# schema_puissance.net
KiCad netlist of a schematic drawn in EAGLE
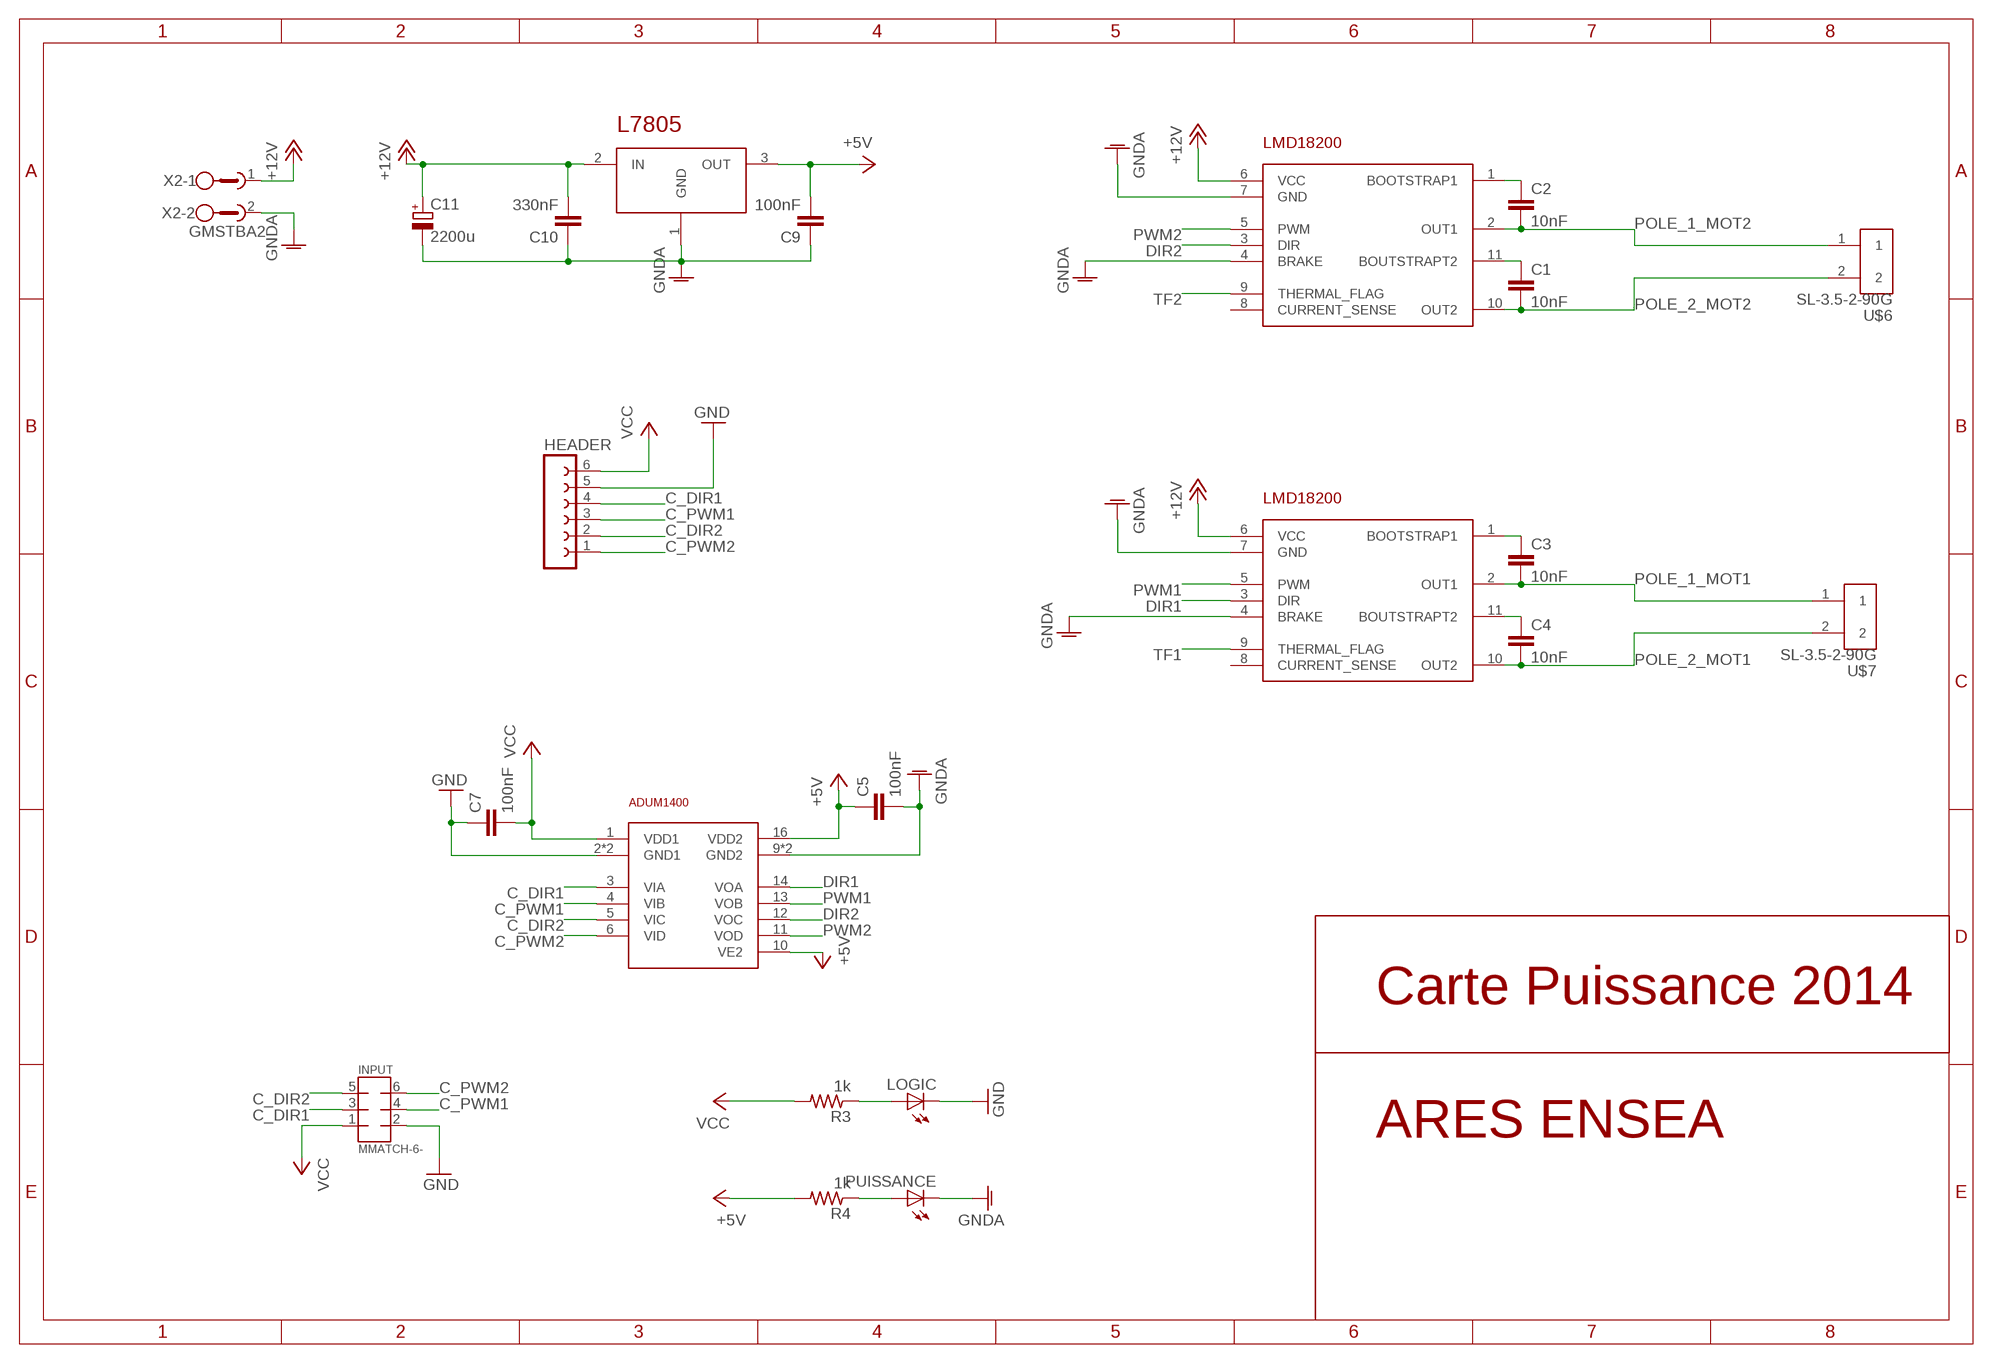
[diagram p0: schematic, sheet 1]

(export (version "E")
  (design (tool "Eeschema 10.0.6"))
  (components
    (comp (ref "C1")
      (value "10nF")
      (footprint "eagle-import:C0805")
      (libsource (lib "eagle-import") (part "C-EUC0805"))
    )
    (comp (ref "C2")
      (value "10nF")
      (footprint "eagle-import:C0805")
      (libsource (lib "eagle-import") (part "C-EUC0805"))
    )
    (comp (ref "C3")
      (value "10nF")
      (footprint "eagle-import:C0805")
      (libsource (lib "eagle-import") (part "C-EUC0805"))
    )
    (comp (ref "C4")
      (value "10nF")
      (footprint "eagle-import:C0805")
      (libsource (lib "eagle-import") (part "C-EUC0805"))
    )
    (comp (ref "C5")
      (value "100nF")
      (footprint "eagle-import:C0805")
      (libsource (lib "eagle-import") (part "C-EUC0805"))
    )
    (comp (ref "C7")
      (value "100nF")
      (footprint "eagle-import:C0805")
      (libsource (lib "eagle-import") (part "C-EUC0805"))
    )
    (comp (ref "C9")
      (value "100nF")
      (footprint "eagle-import:C0805")
      (libsource (lib "eagle-import") (part "C-EUC0805"))
    )
    (comp (ref "C10")
      (value "330nF")
      (footprint "eagle-import:C0805")
      (libsource (lib "eagle-import") (part "C-EUC0805"))
    )
    (comp (ref "C11")
      (value "2200u")
      (footprint "eagle-import:TT5D11")
      (libsource (lib "eagle-import") (part "CPOL-EUTT5D11"))
    )
    (comp (ref "HEADER")
      (value "FE06-1")
      (footprint "eagle-import:FE06")
      (libsource (lib "eagle-import") (part "FE06-1"))
    )
    (comp (ref "INPUT")
      (value "MMATCH-6-")
      (footprint "eagle-import:AMP-215079-6")
      (libsource (lib "eagle-import") (part "MMATCH-6-"))
    )
    (comp (ref "LOGIC")
      (value "LEDSML0805")
      (footprint "eagle-import:SML0805")
      (libsource (lib "eagle-import") (part "LEDSML0805"))
    )
    (comp (ref "PUISSANCE")
      (value "LEDSML0805")
      (footprint "eagle-import:SML0805")
      (libsource (lib "eagle-import") (part "LEDSML0805"))
    )
    (comp (ref "R3")
      (value "1k")
      (footprint "eagle-import:M0805")
      (libsource (lib "eagle-import") (part "R-US_M0805"))
    )
    (comp (ref "R4")
      (value "1k")
      (footprint "eagle-import:M0805")
      (libsource (lib "eagle-import") (part "R-US_M0805"))
    )
    (comp (ref "U$1")
      (value "LMD18200")
      (footprint "eagle-import:LMD18200")
      (libsource (lib "eagle-import") (part "LMD18200"))
    )
    (comp (ref "U$2")
      (value "LMD18200")
      (footprint "eagle-import:LMD18200")
      (libsource (lib "eagle-import") (part "LMD18200"))
    )
    (comp (ref "U$3")
      (value "ADUM1400S")
      (footprint "eagle-import:SO-16W")
      (libsource (lib "eagle-import") (part "ADUM1400S"))
    )
    (comp (ref "U$5")
      (value "L7805TO263")
      (footprint "eagle-import:DPAK")
      (libsource (lib "eagle-import") (part "L7805TO263"))
    )
    (comp (ref "U$6")
      (value "SL-3.5-2-90G")
      (footprint "eagle-import:SL-3.5-2-90G")
      (libsource (lib "eagle-import") (part "SL-3.5-2-90G"))
    )
    (comp (ref "U$7")
      (value "SL-3.5-2-90G")
      (footprint "eagle-import:SL-3.5-2-90G")
      (libsource (lib "eagle-import") (part "SL-3.5-2-90G"))
    )
    (comp (ref "X2")
      (value "GMSTBA2")
      (footprint "eagle-import:GMSTBA2")
      (fields (field (name "MF") "FARNELL") (field (name "MPN") "1757242"))
      (libsource (lib "eagle-import") (part "GMSTBA2"))
    )
  )
  (nets
    (net (code "1") (name "+5V") (class "Default")
      (node (ref "C5") (pin "1") (pinfunction "1_1") (pintype "passive"))
      (node (ref "C9") (pin "2") (pinfunction "2_2") (pintype "passive"))
      (node (ref "R4") (pin "2") (pinfunction "2_2") (pintype "passive"))
      (node (ref "U$3") (pin "10") (pinfunction "VE2_10") (pintype "bidirectional"))
      (node (ref "U$3") (pin "16") (pinfunction "VDD2_16") (pintype "bidirectional"))
      (node (ref "U$5") (pin "3") (pinfunction "OUT_3") (pintype "bidirectional"))
    )
    (net (code "2") (name "+12V") (class "Default")
      (node (ref "C10") (pin "2") (pinfunction "2_2") (pintype "passive"))
      (node (ref "C11") (pin "+") (pinfunction "+_+") (pintype "passive"))
      (node (ref "U$1") (pin "6") (pinfunction "VCC_6") (pintype "bidirectional"))
      (node (ref "U$2") (pin "6") (pinfunction "VCC_6") (pintype "bidirectional"))
      (node (ref "U$5") (pin "2") (pinfunction "IN_2") (pintype "bidirectional"))
      (node (ref "X2") (pin "1") (pinfunction "1_1") (pintype "passive"))
    )
    (net (code "3") (name "/C_DIR1") (class "Default")
      (node (ref "HEADER") (pin "4") (pinfunction "4_4") (pintype "passive"))
      (node (ref "INPUT") (pin "3") (pinfunction "5_3") (pintype "bidirectional"))
      (node (ref "U$3") (pin "3") (pinfunction "VIA_3") (pintype "bidirectional"))
    )
    (net (code "4") (name "/C_DIR2") (class "Default")
      (node (ref "HEADER") (pin "2") (pinfunction "2_2") (pintype "passive"))
      (node (ref "INPUT") (pin "5") (pinfunction "7_5") (pintype "bidirectional"))
      (node (ref "U$3") (pin "5") (pinfunction "VIC_5") (pintype "bidirectional"))
    )
    (net (code "5") (name "/C_PWM1") (class "Default")
      (node (ref "HEADER") (pin "3") (pinfunction "3_3") (pintype "passive"))
      (node (ref "INPUT") (pin "4") (pinfunction "6_4") (pintype "bidirectional"))
      (node (ref "U$3") (pin "4") (pinfunction "VIB_4") (pintype "bidirectional"))
    )
    (net (code "6") (name "/C_PWM2") (class "Default")
      (node (ref "HEADER") (pin "1") (pinfunction "1_1") (pintype "passive"))
      (node (ref "INPUT") (pin "6") (pinfunction "8_6") (pintype "bidirectional"))
      (node (ref "U$3") (pin "6") (pinfunction "VID_6") (pintype "bidirectional"))
    )
    (net (code "7") (name "/DIR1") (class "Default")
      (node (ref "U$1") (pin "3") (pinfunction "DIR_3") (pintype "bidirectional"))
      (node (ref "U$3") (pin "14") (pinfunction "VOA_14") (pintype "bidirectional"))
    )
    (net (code "8") (name "/DIR2") (class "Default")
      (node (ref "U$2") (pin "3") (pinfunction "DIR_3") (pintype "bidirectional"))
      (node (ref "U$3") (pin "12") (pinfunction "VOC_12") (pintype "bidirectional"))
    )
    (net (code "9") (name "/POLE_1_MOT1") (class "Default")
      (node (ref "C3") (pin "2") (pinfunction "2_2") (pintype "passive"))
      (node (ref "U$1") (pin "2") (pinfunction "OUT1_2") (pintype "bidirectional"))
      (node (ref "U$7") (pin "1") (pinfunction "1_1") (pintype "bidirectional"))
    )
    (net (code "10") (name "/POLE_1_MOT2") (class "Default")
      (node (ref "C2") (pin "2") (pinfunction "2_2") (pintype "passive"))
      (node (ref "U$2") (pin "2") (pinfunction "OUT1_2") (pintype "bidirectional"))
      (node (ref "U$6") (pin "1") (pinfunction "1_1") (pintype "bidirectional"))
    )
    (net (code "11") (name "/POLE_2_MOT1") (class "Default")
      (node (ref "C4") (pin "2") (pinfunction "2_2") (pintype "passive"))
      (node (ref "U$1") (pin "10") (pinfunction "OUT2_10") (pintype "bidirectional"))
      (node (ref "U$7") (pin "2") (pinfunction "2_2") (pintype "bidirectional"))
    )
    (net (code "12") (name "/POLE_2_MOT2") (class "Default")
      (node (ref "C1") (pin "2") (pinfunction "2_2") (pintype "passive"))
      (node (ref "U$2") (pin "10") (pinfunction "OUT2_10") (pintype "bidirectional"))
      (node (ref "U$6") (pin "2") (pinfunction "2_2") (pintype "bidirectional"))
    )
    (net (code "13") (name "/PWM1") (class "Default")
      (node (ref "U$1") (pin "5") (pinfunction "PWM_5") (pintype "bidirectional"))
      (node (ref "U$3") (pin "13") (pinfunction "VOB_13") (pintype "bidirectional"))
    )
    (net (code "14") (name "/PWM2") (class "Default")
      (node (ref "U$2") (pin "5") (pinfunction "PWM_5") (pintype "bidirectional"))
      (node (ref "U$3") (pin "11") (pinfunction "VOD_11") (pintype "bidirectional"))
    )
    (net (code "15") (name "/TF1") (class "Default")
      (node (ref "U$1") (pin "9") (pinfunction "THERMAL_FLAG_9") (pintype "bidirectional"))
    )
    (net (code "16") (name "/TF2") (class "Default")
      (node (ref "U$2") (pin "9") (pinfunction "THERMAL_FLAG_9") (pintype "bidirectional"))
    )
    (net (code "17") (name "GND") (class "Default")
      (node (ref "C7") (pin "1") (pinfunction "1_1") (pintype "passive"))
      (node (ref "HEADER") (pin "5") (pinfunction "5_5") (pintype "passive"))
      (node (ref "INPUT") (pin "2") (pinfunction "4_2") (pintype "bidirectional"))
      (node (ref "LOGIC") (pin "C") (pinfunction "C_C") (pintype "passive"))
      (node (ref "U$3") (pin "2") (pinfunction "GND1_2") (pintype "bidirectional"))
      (node (ref "U$3") (pin "8") (pinfunction "GND1_8") (pintype "bidirectional"))
    )
    (net (code "18") (name "GNDA") (class "Default")
      (node (ref "C10") (pin "1") (pinfunction "1_1") (pintype "passive"))
      (node (ref "C11") (pin "-") (pinfunction "-_-") (pintype "passive"))
      (node (ref "C5") (pin "2") (pinfunction "2_2") (pintype "passive"))
      (node (ref "C9") (pin "1") (pinfunction "1_1") (pintype "passive"))
      (node (ref "PUISSANCE") (pin "C") (pinfunction "C_C") (pintype "passive"))
      (node (ref "U$1") (pin "4") (pinfunction "BRAKE_4") (pintype "bidirectional"))
      (node (ref "U$1") (pin "7") (pinfunction "GND_7") (pintype "bidirectional"))
      (node (ref "U$2") (pin "4") (pinfunction "BRAKE_4") (pintype "bidirectional"))
      (node (ref "U$2") (pin "7") (pinfunction "GND_7") (pintype "bidirectional"))
      (node (ref "U$3") (pin "15") (pinfunction "GND2_15") (pintype "bidirectional"))
      (node (ref "U$3") (pin "9") (pinfunction "GND2_9") (pintype "bidirectional"))
      (node (ref "U$5") (pin "1") (pinfunction "GND_1") (pintype "bidirectional"))
      (node (ref "X2") (pin "2") (pinfunction "1_2") (pintype "passive"))
    )
    (net (code "19") (name "Net-(LOGIC-PadA)") (class "Default")
      (node (ref "LOGIC") (pin "A") (pinfunction "A_A") (pintype "passive"))
      (node (ref "R3") (pin "1") (pinfunction "1_1") (pintype "passive"))
    )
    (net (code "20") (name "Net-(PUISSANCE-PadA)") (class "Default")
      (node (ref "PUISSANCE") (pin "A") (pinfunction "A_A") (pintype "passive"))
      (node (ref "R4") (pin "1") (pinfunction "1_1") (pintype "passive"))
    )
    (net (code "21") (name "Net-(U$1-BOOTSTRAP1)") (class "Default")
      (node (ref "C3") (pin "1") (pinfunction "1_1") (pintype "passive"))
      (node (ref "U$1") (pin "1") (pinfunction "BOOTSTRAP1_1") (pintype "bidirectional"))
    )
    (net (code "22") (name "Net-(U$1-BOUTSTRAPT2)") (class "Default")
      (node (ref "C4") (pin "1") (pinfunction "1_1") (pintype "passive"))
      (node (ref "U$1") (pin "11") (pinfunction "BOUTSTRAPT2_11") (pintype "bidirectional"))
    )
    (net (code "23") (name "Net-(U$2-BOOTSTRAP1)") (class "Default")
      (node (ref "C2") (pin "1") (pinfunction "1_1") (pintype "passive"))
      (node (ref "U$2") (pin "1") (pinfunction "BOOTSTRAP1_1") (pintype "bidirectional"))
    )
    (net (code "24") (name "Net-(U$2-BOUTSTRAPT2)") (class "Default")
      (node (ref "C1") (pin "1") (pinfunction "1_1") (pintype "passive"))
      (node (ref "U$2") (pin "11") (pinfunction "BOUTSTRAPT2_11") (pintype "bidirectional"))
    )
    (net (code "25") (name "VCC") (class "Default")
      (node (ref "C7") (pin "2") (pinfunction "2_2") (pintype "passive"))
      (node (ref "HEADER") (pin "6") (pinfunction "6_6") (pintype "passive"))
      (node (ref "INPUT") (pin "1") (pinfunction "3_1") (pintype "bidirectional"))
      (node (ref "R3") (pin "2") (pinfunction "2_2") (pintype "passive"))
      (node (ref "U$3") (pin "1") (pinfunction "VDD1_1") (pintype "bidirectional"))
    )
    (net (code "26") (name "unconnected-(U$1-CURRENT_SENSE-Pad8)") (class "Default")
      (node (ref "U$1") (pin "8") (pinfunction "CURRENT_SENSE_8") (pintype "bidirectional"))
    )
    (net (code "27") (name "unconnected-(U$2-CURRENT_SENSE-Pad8)") (class "Default")
      (node (ref "U$2") (pin "8") (pinfunction "CURRENT_SENSE_8") (pintype "bidirectional"))
    )
  )
)
